# design.net
KiCad netlist of a schematic drawn in EAGLE
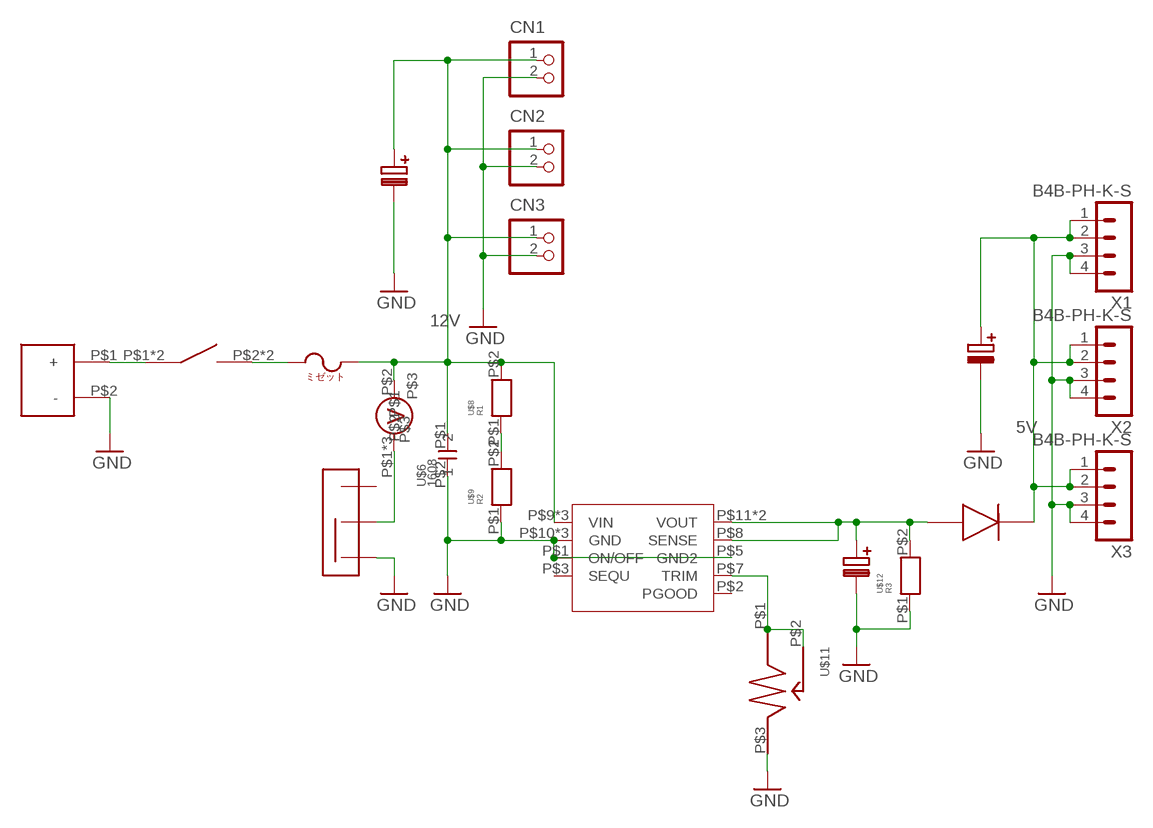
[diagram p0: schematic, sheet 1]

(export (version "E")
  (design (tool "Eeschema 10.0.6"))
  (components
    (comp (ref "CN1")
      (value "S2B-XH-A")
      (footprint "eagle-import:S2B-XH-A")
      (libsource (lib "eagle-import") (part "S2B-XH-A"))
    )
    (comp (ref "CN2")
      (value "S2B-XH-A")
      (footprint "eagle-import:S2B-XH-A")
      (libsource (lib "eagle-import") (part "S2B-XH-A"))
    )
    (comp (ref "CN3")
      (value "S2B-XH-A")
      (footprint "eagle-import:S2B-XH-A")
      (libsource (lib "eagle-import") (part "S2B-XH-A"))
    )
    (comp (ref "U$1")
      (value "XT60")
      (footprint "eagle-import:XT60")
      (libsource (lib "eagle-import") (part "XT60"))
    )
    (comp (ref "U$2") (value "MF") (footprint "eagle-import:ｍｆ") (libsource (lib "eagle-import") (part "MF")))
    (comp (ref "U$3") (value "V") (footprint "eagle-import:V") (libsource (lib "eagle-import") (part "V")))
    (comp (ref "U$4")
      (value "SW3")
      (footprint "eagle-import:SW3")
      (libsource (lib "eagle-import") (part "SW3"))
    )
    (comp (ref "U$5")
      (value "DCDC")
      (footprint "eagle-import:DC-DC")
      (libsource (lib "eagle-import") (part "DCDC"))
    )
    (comp (ref "U$6")
      (value "1608")
      (footprint "eagle-import:CON")
      (libsource (lib "eagle-import") (part "1608"))
    )
    (comp (ref "U$7")
      (value "25V100")
      (footprint "eagle-import:25V100")
      (libsource (lib "eagle-import") (part "25V100"))
    )
    (comp (ref "U$8")
      (value "R1")
      (footprint "eagle-import:1608")
      (libsource (lib "eagle-import") (part "R"))
    )
    (comp (ref "U$9")
      (value "R2")
      (footprint "eagle-import:1608")
      (libsource (lib "eagle-import") (part "R"))
    )
    (comp (ref "U$10")
      (value "40V5A")
      (footprint "eagle-import:40V5A")
      (libsource (lib "eagle-import") (part "40V5A"))
    )
    (comp (ref "U$11")
      (value "VR")
      (footprint "eagle-import:VR")
      (libsource (lib "eagle-import") (part "VR"))
    )
    (comp (ref "U$12")
      (value "R3")
      (footprint "eagle-import:1608")
      (libsource (lib "eagle-import") (part "R"))
    )
    (comp (ref "U$15")
      (value "25V100")
      (footprint "eagle-import:25V100")
      (libsource (lib "eagle-import") (part "25V100"))
    )
    (comp (ref "U$16")
      (value "SSW")
      (footprint "eagle-import:SSW")
      (libsource (lib "eagle-import") (part "SSW"))
    )
    (comp (ref "U$19")
      (value "25V100")
      (footprint "eagle-import:25V100")
      (libsource (lib "eagle-import") (part "25V100"))
    )
    (comp (ref "X1")
      (value "B4B-PH-K-S")
      (footprint "eagle-import:B4B-PH-K-S")
      (libsource (lib "eagle-import") (part "B4B-PH-K-S"))
    )
    (comp (ref "X2")
      (value "B4B-PH-K-S")
      (footprint "eagle-import:B4B-PH-K-S")
      (libsource (lib "eagle-import") (part "B4B-PH-K-S"))
    )
    (comp (ref "X3")
      (value "B4B-PH-K-S")
      (footprint "eagle-import:B4B-PH-K-S")
      (libsource (lib "eagle-import") (part "B4B-PH-K-S"))
    )
  )
  (nets
    (net (code "1") (name "/5V") (class "Default")
      (node (ref "U$10") (pin "P$2") (pinfunction "P$2_P$2") (pintype "bidirectional"))
      (node (ref "U$19") (pin "P$1") (pinfunction "P$1_P$1") (pintype "bidirectional"))
      (node (ref "X1") (pin "1") (pinfunction "1_1") (pintype "passive"))
      (node (ref "X1") (pin "2") (pinfunction "2_2") (pintype "passive"))
      (node (ref "X2") (pin "1") (pinfunction "1_1") (pintype "passive"))
      (node (ref "X2") (pin "2") (pinfunction "2_2") (pintype "passive"))
      (node (ref "X3") (pin "1") (pinfunction "1_1") (pintype "passive"))
      (node (ref "X3") (pin "2") (pinfunction "2_2") (pintype "passive"))
    )
    (net (code "2") (name "/12V") (class "Default")
      (node (ref "CN1") (pin "1") (pinfunction "1_1") (pintype "passive"))
      (node (ref "CN2") (pin "1") (pinfunction "1_1") (pintype "passive"))
      (node (ref "CN3") (pin "1") (pinfunction "1_1") (pintype "passive"))
      (node (ref "U$15") (pin "P$1") (pinfunction "P$1_P$1") (pintype "bidirectional"))
      (node (ref "U$2") (pin "P$3") (pinfunction "P$2_P$3") (pintype "bidirectional"))
      (node (ref "U$2") (pin "P$4") (pinfunction "P$2_P$4") (pintype "bidirectional"))
      (node (ref "U$3") (pin "P$2") (pinfunction "P$2_P$2") (pintype "bidirectional"))
      (node (ref "U$5") (pin "P$14") (pinfunction "VIN_P$14") (pintype "bidirectional"))
      (node (ref "U$5") (pin "P$15") (pinfunction "VIN_P$15") (pintype "bidirectional"))
      (node (ref "U$5") (pin "P$9") (pinfunction "VIN_P$9") (pintype "bidirectional"))
      (node (ref "U$6") (pin "P$1") (pinfunction "1_P$1") (pintype "bidirectional"))
      (node (ref "U$8") (pin "P$2") (pinfunction "P$2_P$2") (pintype "bidirectional"))
    )
    (net (code "3") (name "GND") (class "Default")
      (node (ref "CN1") (pin "2") (pinfunction "2_2") (pintype "passive"))
      (node (ref "CN2") (pin "2") (pinfunction "2_2") (pintype "passive"))
      (node (ref "CN3") (pin "2") (pinfunction "2_2") (pintype "passive"))
      (node (ref "U$1") (pin "P$2") (pinfunction "-_P$2") (pintype "bidirectional"))
      (node (ref "U$11") (pin "P$3") (pinfunction "P$3_P$3") (pintype "bidirectional"))
      (node (ref "U$12") (pin "P$1") (pinfunction "P$1_P$1") (pintype "bidirectional"))
      (node (ref "U$15") (pin "P$2") (pinfunction "P$2_P$2") (pintype "bidirectional"))
      (node (ref "U$16") (pin "P$1") (pinfunction "P$1_P$1") (pintype "bidirectional"))
      (node (ref "U$19") (pin "P$2") (pinfunction "P$2_P$2") (pintype "bidirectional"))
      (node (ref "U$5") (pin "P$1") (pinfunction "ON/OFF_P$1") (pintype "bidirectional"))
      (node (ref "U$5") (pin "P$10") (pinfunction "GND_P$10") (pintype "bidirectional"))
      (node (ref "U$5") (pin "P$16") (pinfunction "GND_P$16") (pintype "bidirectional"))
      (node (ref "U$5") (pin "P$17") (pinfunction "GND_P$17") (pintype "bidirectional"))
      (node (ref "U$5") (pin "P$5") (pinfunction "GND2_P$5") (pintype "bidirectional"))
      (node (ref "U$6") (pin "P$2") (pinfunction "2_P$2") (pintype "bidirectional"))
      (node (ref "U$7") (pin "P$2") (pinfunction "P$2_P$2") (pintype "bidirectional"))
      (node (ref "U$9") (pin "P$1") (pinfunction "P$1_P$1") (pintype "bidirectional"))
      (node (ref "X1") (pin "3") (pinfunction "3_3") (pintype "passive"))
      (node (ref "X1") (pin "4") (pinfunction "4_4") (pintype "passive"))
      (node (ref "X2") (pin "3") (pinfunction "3_3") (pintype "passive"))
      (node (ref "X2") (pin "4") (pinfunction "4_4") (pintype "passive"))
      (node (ref "X3") (pin "3") (pinfunction "3_3") (pintype "passive"))
      (node (ref "X3") (pin "4") (pinfunction "4_4") (pintype "passive"))
    )
    (net (code "4") (name "Net-(U$1-+)") (class "Default")
      (node (ref "U$1") (pin "P$1") (pinfunction "+_P$1") (pintype "bidirectional"))
      (node (ref "U$4") (pin "P$1") (pinfunction "P$1_P$1") (pintype "bidirectional"))
      (node (ref "U$4") (pin "P$3") (pinfunction "P$1_P$3") (pintype "bidirectional"))
    )
    (net (code "5") (name "Net-(U$2-P$1-PadP$2)") (class "Default")
      (node (ref "U$2") (pin "P$1") (pinfunction "P$1_P$1") (pintype "bidirectional"))
      (node (ref "U$2") (pin "P$2") (pinfunction "P$1_P$2") (pintype "bidirectional"))
      (node (ref "U$4") (pin "P$2") (pinfunction "P$2_P$2") (pintype "bidirectional"))
      (node (ref "U$4") (pin "P$4") (pinfunction "P$2_P$4") (pintype "bidirectional"))
    )
    (net (code "6") (name "Net-(U$5-SENSE)") (class "Default")
      (node (ref "U$10") (pin "P$1") (pinfunction "P$1_P$1") (pintype "bidirectional"))
      (node (ref "U$12") (pin "P$2") (pinfunction "P$2_P$2") (pintype "bidirectional"))
      (node (ref "U$5") (pin "P$11") (pinfunction "VOUT_P$11") (pintype "bidirectional"))
      (node (ref "U$5") (pin "P$18") (pinfunction "VOUT_P$18") (pintype "bidirectional"))
      (node (ref "U$5") (pin "P$8") (pinfunction "SENSE_P$8") (pintype "bidirectional"))
      (node (ref "U$7") (pin "P$1") (pinfunction "P$1_P$1") (pintype "bidirectional"))
    )
    (net (code "7") (name "Net-(U$5-TRIM)") (class "Default")
      (node (ref "U$11") (pin "P$1") (pinfunction "P$1_P$1") (pintype "bidirectional"))
      (node (ref "U$11") (pin "P$2") (pinfunction "P$2_P$2") (pintype "bidirectional"))
      (node (ref "U$5") (pin "P$7") (pinfunction "TRIM_P$7") (pintype "bidirectional"))
    )
    (net (code "8") (name "Net-(U$8-PadP$1)") (class "Default")
      (node (ref "U$8") (pin "P$1") (pinfunction "P$1_P$1") (pintype "bidirectional"))
      (node (ref "U$9") (pin "P$2") (pinfunction "P$2_P$2") (pintype "bidirectional"))
    )
    (net (code "9") (name "Net-(U$16-P$2)") (class "Default")
      (node (ref "U$16") (pin "P$3") (pinfunction "P$2_P$3") (pintype "bidirectional"))
      (node (ref "U$3") (pin "P$1") (pinfunction "P$1_P$1") (pintype "bidirectional"))
      (node (ref "U$3") (pin "P$4") (pinfunction "P$1_P$4") (pintype "bidirectional"))
      (node (ref "U$3") (pin "P$5") (pinfunction "P$1_P$5") (pintype "bidirectional"))
    )
    (net (code "10") (name "unconnected-(U$3-PadP$3)") (class "Default")
      (node (ref "U$3") (pin "P$3") (pinfunction "P$3_P$3") (pintype "bidirectional"))
    )
    (net (code "11") (name "unconnected-(U$5-PGOOD-PadP$2)") (class "Default")
      (node (ref "U$5") (pin "P$2") (pinfunction "PGOOD_P$2") (pintype "bidirectional"))
    )
    (net (code "12") (name "unconnected-(U$5-SEQU-PadP$3)") (class "Default")
      (node (ref "U$5") (pin "P$3") (pinfunction "SEQU_P$3") (pintype "bidirectional"))
    )
    (net (code "13") (name "unconnected-(U$16-P$3-PadP$2)") (class "Default")
      (node (ref "U$16") (pin "P$2") (pinfunction "P$3_P$2") (pintype "bidirectional"))
    )
  )
)
